# TestAdapter.net
KiCad netlist of a schematic drawn in EAGLE
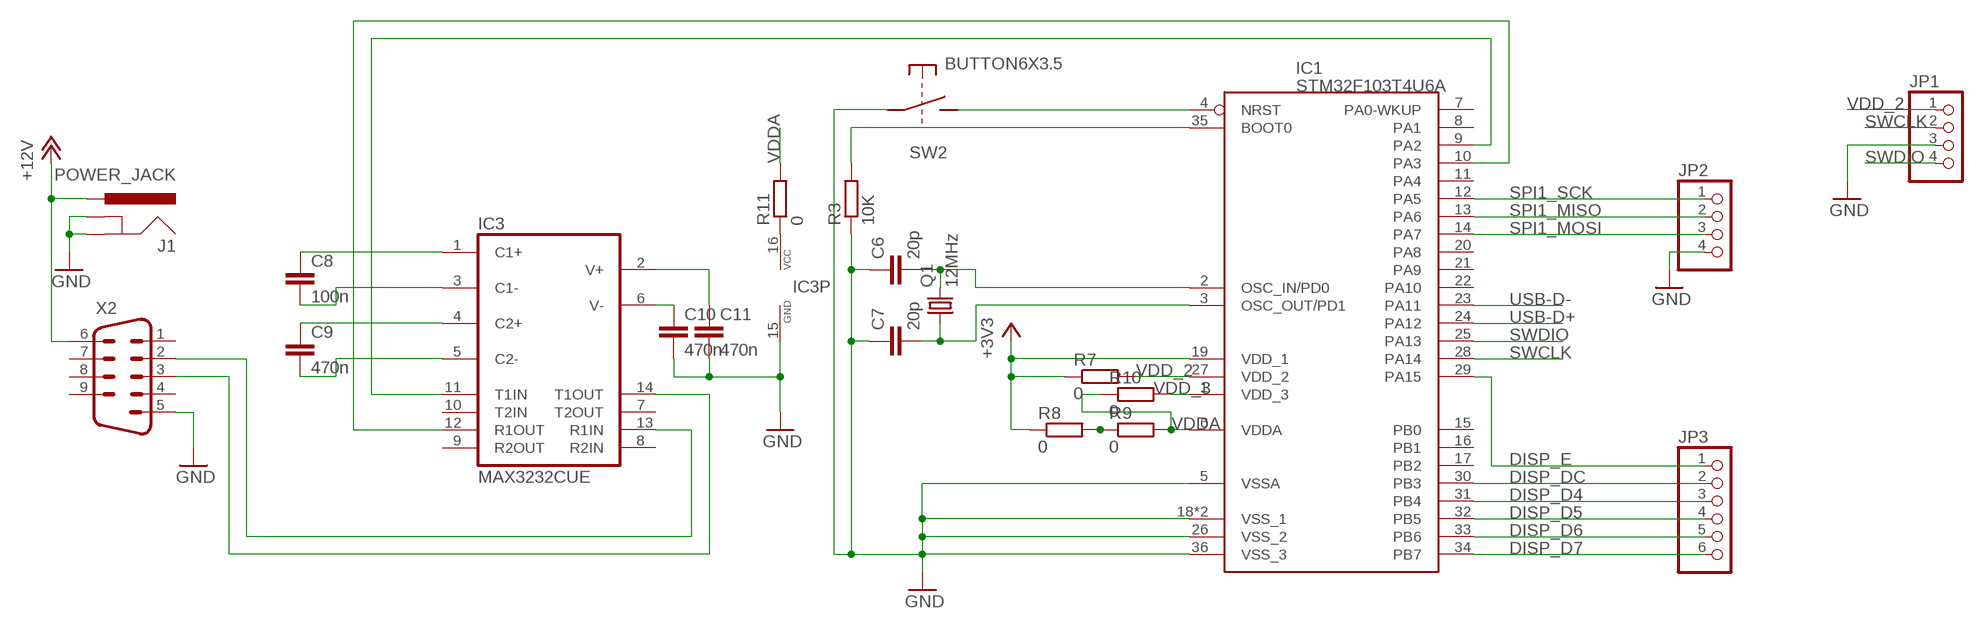
[diagram p0: schematic, sheet 1]
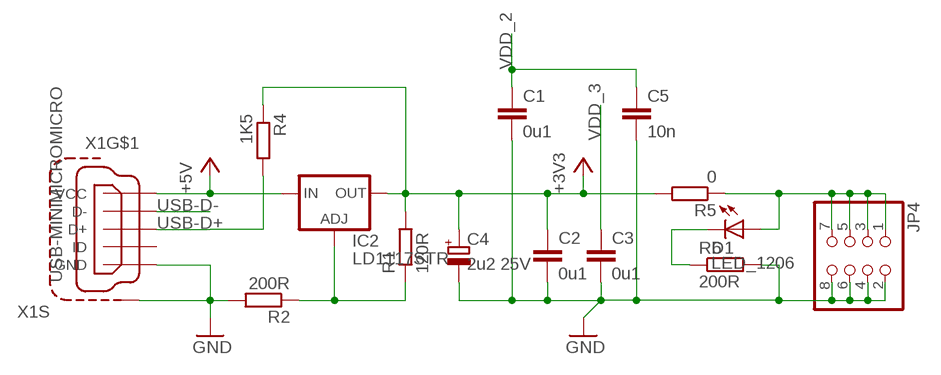
[diagram p1: schematic, sheet 2]

(export (version "E")
  (design (tool "Eeschema 10.0.6"))
  (components
    (comp (ref "C1")
      (value "0u1")
      (footprint "eagle-import:CAP0805")
      (libsource (lib "eagle-import") (part "CAP_0805"))
    )
    (comp (ref "C2")
      (value "0u1")
      (footprint "eagle-import:CAP0805")
      (libsource (lib "eagle-import") (part "CAP_0805"))
    )
    (comp (ref "C3")
      (value "0u1")
      (footprint "eagle-import:CAP0805")
      (libsource (lib "eagle-import") (part "CAP_0805"))
    )
    (comp (ref "C4")
      (value "2u2 25V")
      (footprint "eagle-import:CAPMP3317X180")
      (libsource (lib "eagle-import") (part "CAP-POL_CAPE3216-A"))
    )
    (comp (ref "C5")
      (value "10n")
      (footprint "eagle-import:CAP0805")
      (libsource (lib "eagle-import") (part "CAP_0805"))
    )
    (comp (ref "D1")
      (value "LED_1206")
      (footprint "eagle-import:LED1206")
      (libsource (lib "eagle-import") (part "LED_1206"))
    )
    (comp (ref "IC2")
      (value "LD1117STR")
      (footprint "eagle-import:SOT230P700X180-4")
      (libsource (lib "eagle-import") (part "VREG-ADJLD1117S"))
    )
    (comp (ref "JP4")
      (value "PINHD-2X4")
      (footprint "eagle-import:2X04")
      (libsource (lib "eagle-import") (part "PINHD-2X4"))
    )
    (comp (ref "R1")
      (value "120R")
      (footprint "eagle-import:RESC2012X50")
      (libsource (lib "eagle-import") (part "R_R0805"))
    )
    (comp (ref "R2")
      (value "200R")
      (footprint "eagle-import:RESC2012X50")
      (libsource (lib "eagle-import") (part "R_R0805"))
    )
    (comp (ref "R4")
      (value "1K5")
      (footprint "eagle-import:RESC2012X50")
      (libsource (lib "eagle-import") (part "R_R0805"))
    )
    (comp (ref "R5")
      (value "0")
      (footprint "eagle-import:RESC2012X50")
      (libsource (lib "eagle-import") (part "R_R0805"))
    )
    (comp (ref "R6")
      (value "200R")
      (footprint "eagle-import:RESC2012X50")
      (libsource (lib "eagle-import") (part "R_R0805"))
    )
    (comp (ref "X1")
      (value "USB-MINIMICROMICRO")
      (footprint "eagle-import:USB-B-MICRO-SMD")
      (libsource (lib "eagle-import") (part "USB-MINIMICROMICRO"))
    )
    (comp (ref "C6")
      (value "20p")
      (footprint "eagle-import:CAP0805")
      (libsource (lib "eagle-import") (part "CAP_0805"))
    )
    (comp (ref "C7")
      (value "20p")
      (footprint "eagle-import:CAP0805")
      (libsource (lib "eagle-import") (part "CAP_0805"))
    )
    (comp (ref "C8")
      (value "100n")
      (footprint "eagle-import:CAP0805")
      (libsource (lib "eagle-import") (part "CAP_0805"))
    )
    (comp (ref "C9")
      (value "470n")
      (footprint "eagle-import:CAP0805")
      (libsource (lib "eagle-import") (part "CAP_0805"))
    )
    (comp (ref "C10")
      (value "470n")
      (footprint "eagle-import:CAP0805")
      (libsource (lib "eagle-import") (part "CAP_0805"))
    )
    (comp (ref "C11")
      (value "470n")
      (footprint "eagle-import:CAP0805")
      (libsource (lib "eagle-import") (part "CAP_0805"))
    )
    (comp (ref "IC1")
      (value "STM32F103T4U6A")
      (footprint "eagle-import:QFN50P606X606X100-36")
      (libsource (lib "eagle-import") (part "STM32F103T4U6A"))
    )
    (comp (ref "IC3")
      (value "MAX3232CUE")
      (footprint "eagle-import:TSSOP16")
      (fields (field (name "MF") "MAXIM") (field (name "MPN") "MAX3232CUE+"))
      (libsource (lib "eagle-import") (part "MAX3232UEC"))
    )
    (comp (ref "J1")
      (value "POWER_JACK")
      (footprint "eagle-import:POWER_JACK_PTH")
      (libsource (lib "eagle-import") (part "POWER_JACK"))
    )
    (comp (ref "JP1")
      (value "PINHD-1X4")
      (footprint "eagle-import:1X04")
      (libsource (lib "eagle-import") (part "PINHD-1X4"))
    )
    (comp (ref "JP2")
      (value "PINHD-1X4")
      (footprint "eagle-import:1X04")
      (libsource (lib "eagle-import") (part "PINHD-1X4"))
    )
    (comp (ref "JP3")
      (value "PINHD-1X6")
      (footprint "eagle-import:1X06")
      (libsource (lib "eagle-import") (part "PINHD-1X6"))
    )
    (comp (ref "Q1")
      (value "12MHz")
      (footprint "eagle-import:CRYSTAL-5025")
      (libsource (lib "eagle-import") (part "CRYSTAL5032"))
    )
    (comp (ref "R3")
      (value "10K")
      (footprint "eagle-import:RESC2012X50")
      (libsource (lib "eagle-import") (part "R_R0805"))
    )
    (comp (ref "R7")
      (value "0")
      (footprint "eagle-import:RESC2012X50")
      (libsource (lib "eagle-import") (part "R_R0805"))
    )
    (comp (ref "R8")
      (value "0")
      (footprint "eagle-import:RESC2012X50")
      (libsource (lib "eagle-import") (part "R_R0805"))
    )
    (comp (ref "R9")
      (value "0")
      (footprint "eagle-import:RESC2012X50")
      (libsource (lib "eagle-import") (part "R_R0805"))
    )
    (comp (ref "R10")
      (value "0")
      (footprint "eagle-import:RESC2012X50")
      (libsource (lib "eagle-import") (part "R_R0805"))
    )
    (comp (ref "R11")
      (value "0")
      (footprint "eagle-import:RESC2012X50")
      (libsource (lib "eagle-import") (part "R_R0805"))
    )
    (comp (ref "SW2")
      (value "BUTTON6X3.5")
      (footprint "eagle-import:SW-6X3.5")
      (libsource (lib "eagle-import") (part "BUTTON6X3.5"))
    )
    (comp (ref "X2")
      (value "M09-182")
      (footprint "eagle-import:182-009-MALE")
      (libsource (lib "eagle-import") (part "M09-182"))
    )
  )
  (nets
    (net (code "1") (name "+3V3") (class "Default")
      (node (ref "C2") (pin "1") (pinfunction "1_1") (pintype "passive"))
      (node (ref "C4") (pin "1") (pinfunction "+_1") (pintype "passive"))
      (node (ref "IC1") (pin "19") (pinfunction "VDD_1_19") (pintype "power_in"))
      (node (ref "IC2") (pin "2") (pinfunction "OUT_2") (pintype "passive"))
      (node (ref "IC2") (pin "4") (pinfunction "OUT_4") (pintype "passive"))
      (node (ref "R1") (pin "2") (pinfunction "2_2") (pintype "passive"))
      (node (ref "R4") (pin "1") (pinfunction "1_1") (pintype "passive"))
      (node (ref "R5") (pin "2") (pinfunction "2_2") (pintype "passive"))
      (node (ref "R7") (pin "1") (pinfunction "1_1") (pintype "passive"))
      (node (ref "R8") (pin "1") (pinfunction "1_1") (pintype "passive"))
    )
    (net (code "2") (name "+5V") (class "Default")
      (node (ref "IC2") (pin "3") (pinfunction "IN_3") (pintype "input"))
      (node (ref "X1") (pin "VBUS") (pinfunction "VCC_VBUS") (pintype "passive"))
    )
    (net (code "3") (name "+12V") (class "Default")
      (node (ref "J1") (pin "PWR") (pinfunction "PWR_PWR") (pintype "bidirectional"))
      (node (ref "X2") (pin "6") (pinfunction "6_6") (pintype "passive"))
    )
    (net (code "4") (name "DISP_D4") (class "Default")
      (node (ref "IC1") (pin "31") (pinfunction "PB4_31") (pintype "bidirectional"))
      (node (ref "JP3") (pin "3") (pinfunction "3_3") (pintype "passive"))
    )
    (net (code "5") (name "DISP_D5") (class "Default")
      (node (ref "IC1") (pin "32") (pinfunction "PB5_32") (pintype "bidirectional"))
      (node (ref "JP3") (pin "4") (pinfunction "4_4") (pintype "passive"))
    )
    (net (code "6") (name "DISP_D6") (class "Default")
      (node (ref "IC1") (pin "33") (pinfunction "PB6_33") (pintype "bidirectional"))
      (node (ref "JP3") (pin "5") (pinfunction "5_5") (pintype "passive"))
    )
    (net (code "7") (name "DISP_D7") (class "Default")
      (node (ref "IC1") (pin "34") (pinfunction "PB7_34") (pintype "bidirectional"))
      (node (ref "JP3") (pin "6") (pinfunction "6_6") (pintype "passive"))
    )
    (net (code "8") (name "DISP_DC") (class "Default")
      (node (ref "IC1") (pin "30") (pinfunction "PB3_30") (pintype "bidirectional"))
      (node (ref "JP3") (pin "2") (pinfunction "2_2") (pintype "passive"))
    )
    (net (code "9") (name "DISP_E") (class "Default")
      (node (ref "IC1") (pin "29") (pinfunction "PA15_29") (pintype "bidirectional"))
      (node (ref "JP3") (pin "1") (pinfunction "1_1") (pintype "passive"))
    )
    (net (code "10") (name "GND") (class "Default")
      (node (ref "C1") (pin "2") (pinfunction "2_2") (pintype "passive"))
      (node (ref "C10") (pin "2") (pinfunction "2_2") (pintype "passive"))
      (node (ref "C11") (pin "2") (pinfunction "2_2") (pintype "passive"))
      (node (ref "C2") (pin "2") (pinfunction "2_2") (pintype "passive"))
      (node (ref "C3") (pin "2") (pinfunction "2_2") (pintype "passive"))
      (node (ref "C4") (pin "2") (pinfunction "-_2") (pintype "passive"))
      (node (ref "C5") (pin "2") (pinfunction "2_2") (pintype "passive"))
      (node (ref "C6") (pin "1") (pinfunction "1_1") (pintype "passive"))
      (node (ref "C7") (pin "1") (pinfunction "1_1") (pintype "passive"))
      (node (ref "IC1") (pin "18") (pinfunction "VSS_1_18") (pintype "power_in"))
      (node (ref "IC1") (pin "26") (pinfunction "VSS_2_26") (pintype "power_in"))
      (node (ref "IC1") (pin "36") (pinfunction "VSS_3_36") (pintype "power_in"))
      (node (ref "IC1") (pin "5") (pinfunction "VSSA_5") (pintype "power_in"))
      (node (ref "IC1") (pin "P$1") (pinfunction "VSS_1_P$1") (pintype "power_in"))
      (node (ref "IC3") (pin "15") (pinfunction "GND_15") (pintype "power_in"))
      (node (ref "J1") (pin "GND") (pinfunction "GND_GND") (pintype "bidirectional"))
      (node (ref "J1") (pin "GNDBREAK") (pinfunction "GNDBREAK_GNDBREAK") (pintype "bidirectional"))
      (node (ref "JP1") (pin "3") (pinfunction "3_3") (pintype "passive"))
      (node (ref "JP2") (pin "4") (pinfunction "4_4") (pintype "passive"))
      (node (ref "JP4") (pin "2") (pinfunction "2_2") (pintype "passive"))
      (node (ref "JP4") (pin "4") (pinfunction "4_4") (pintype "passive"))
      (node (ref "JP4") (pin "6") (pinfunction "6_6") (pintype "passive"))
      (node (ref "JP4") (pin "8") (pinfunction "8_8") (pintype "passive"))
      (node (ref "R2") (pin "2") (pinfunction "2_2") (pintype "passive"))
      (node (ref "R3") (pin "1") (pinfunction "1_1") (pintype "passive"))
      (node (ref "R6") (pin "2") (pinfunction "2_2") (pintype "passive"))
      (node (ref "SW2") (pin "1") (pinfunction "1_1") (pintype "passive"))
      (node (ref "X1") (pin "GND") (pinfunction "GND_GND") (pintype "passive"))
      (node (ref "X1") (pin "SHIELD1") (pinfunction "S1_SHIELD1") (pintype "passive"))
      (node (ref "X1") (pin "SHIELD2") (pinfunction "S1_SHIELD2") (pintype "passive"))
      (node (ref "X1") (pin "SHIELD3") (pinfunction "S1_SHIELD3") (pintype "passive"))
      (node (ref "X2") (pin "5") (pinfunction "5_5") (pintype "passive"))
    )
    (net (code "11") (name "Net-(D1-PadA)") (class "Default")
      (node (ref "D1") (pin "A") (pinfunction "A_A") (pintype "passive"))
      (node (ref "JP4") (pin "1") (pinfunction "1_1") (pintype "passive"))
      (node (ref "JP4") (pin "3") (pinfunction "3_3") (pintype "passive"))
      (node (ref "JP4") (pin "5") (pinfunction "5_5") (pintype "passive"))
      (node (ref "JP4") (pin "7") (pinfunction "7_7") (pintype "passive"))
      (node (ref "R5") (pin "1") (pinfunction "1_1") (pintype "passive"))
    )
    (net (code "12") (name "Net-(D1-PadC)") (class "Default")
      (node (ref "D1") (pin "C") (pinfunction "C_C") (pintype "passive"))
      (node (ref "R6") (pin "1") (pinfunction "1_1") (pintype "passive"))
    )
    (net (code "13") (name "Net-(IC1-BOOT0)") (class "Default")
      (node (ref "IC1") (pin "35") (pinfunction "BOOT0_35") (pintype "bidirectional"))
      (node (ref "R3") (pin "2") (pinfunction "2_2") (pintype "passive"))
    )
    (net (code "14") (name "Net-(IC1-NRST)") (class "Default")
      (node (ref "IC1") (pin "4") (pinfunction "NRST_4") (pintype "bidirectional"))
      (node (ref "SW2") (pin "2") (pinfunction "2_2") (pintype "passive"))
    )
    (net (code "15") (name "Net-(IC1-OSC_IN{slash}PD0)") (class "Default")
      (node (ref "C6") (pin "2") (pinfunction "2_2") (pintype "passive"))
      (node (ref "IC1") (pin "2") (pinfunction "OSC_IN/PD0_2") (pintype "bidirectional"))
      (node (ref "Q1") (pin "P$2") (pinfunction "2_P$2") (pintype "passive"))
    )
    (net (code "16") (name "Net-(IC1-OSC_OUT{slash}PD1)") (class "Default")
      (node (ref "C7") (pin "2") (pinfunction "2_2") (pintype "passive"))
      (node (ref "IC1") (pin "3") (pinfunction "OSC_OUT/PD1_3") (pintype "bidirectional"))
      (node (ref "Q1") (pin "P$1") (pinfunction "1_P$1") (pintype "passive"))
    )
    (net (code "17") (name "Net-(IC1-PA2)") (class "Default")
      (node (ref "IC1") (pin "9") (pinfunction "PA2_9") (pintype "bidirectional"))
      (node (ref "IC3") (pin "11") (pinfunction "T1IN_11") (pintype "input"))
    )
    (net (code "18") (name "Net-(IC1-PA3)") (class "Default")
      (node (ref "IC1") (pin "10") (pinfunction "PA3_10") (pintype "bidirectional"))
      (node (ref "IC3") (pin "12") (pinfunction "R1OUT_12") (pintype "output"))
    )
    (net (code "19") (name "Net-(IC2-ADJ)") (class "Default")
      (node (ref "IC2") (pin "1") (pinfunction "ADJ_1") (pintype "input"))
      (node (ref "R1") (pin "1") (pinfunction "1_1") (pintype "passive"))
      (node (ref "R2") (pin "1") (pinfunction "1_1") (pintype "passive"))
    )
    (net (code "20") (name "Net-(IC3A-C1+)") (class "Default")
      (node (ref "C8") (pin "1") (pinfunction "1_1") (pintype "passive"))
      (node (ref "IC3") (pin "1") (pinfunction "C1+_1") (pintype "bidirectional"))
    )
    (net (code "21") (name "Net-(IC3A-C1-)") (class "Default")
      (node (ref "C8") (pin "2") (pinfunction "2_2") (pintype "passive"))
      (node (ref "IC3") (pin "3") (pinfunction "C1-_3") (pintype "bidirectional"))
    )
    (net (code "22") (name "Net-(IC3A-C2+)") (class "Default")
      (node (ref "C9") (pin "1") (pinfunction "1_1") (pintype "passive"))
      (node (ref "IC3") (pin "4") (pinfunction "C2+_4") (pintype "bidirectional"))
    )
    (net (code "23") (name "Net-(IC3A-C2-)") (class "Default")
      (node (ref "C9") (pin "2") (pinfunction "2_2") (pintype "passive"))
      (node (ref "IC3") (pin "5") (pinfunction "C2-_5") (pintype "bidirectional"))
    )
    (net (code "24") (name "Net-(IC3A-R1IN)") (class "Default")
      (node (ref "IC3") (pin "13") (pinfunction "R1IN_13") (pintype "input"))
      (node (ref "X2") (pin "2") (pinfunction "2_2") (pintype "passive"))
    )
    (net (code "25") (name "Net-(IC3A-T1OUT)") (class "Default")
      (node (ref "IC3") (pin "14") (pinfunction "T1OUT_14") (pintype "output"))
      (node (ref "X2") (pin "3") (pinfunction "3_3") (pintype "passive"))
    )
    (net (code "26") (name "Net-(IC3A-V+)") (class "Default")
      (node (ref "C11") (pin "1") (pinfunction "1_1") (pintype "passive"))
      (node (ref "IC3") (pin "2") (pinfunction "V+_2") (pintype "bidirectional"))
    )
    (net (code "27") (name "Net-(IC3A-V-)") (class "Default")
      (node (ref "C10") (pin "1") (pinfunction "1_1") (pintype "passive"))
      (node (ref "IC3") (pin "6") (pinfunction "V-_6") (pintype "bidirectional"))
    )
    (net (code "28") (name "Net-(IC3B-VCC)") (class "Default")
      (node (ref "IC3") (pin "16") (pinfunction "VCC_16") (pintype "power_in"))
      (node (ref "R11") (pin "1") (pinfunction "1_1") (pintype "passive"))
    )
    (net (code "29") (name "Net-(R8-Pad2)") (class "Default")
      (node (ref "R8") (pin "2") (pinfunction "2_2") (pintype "passive"))
      (node (ref "R9") (pin "1") (pinfunction "1_1") (pintype "passive"))
    )
    (net (code "30") (name "SPI1_MISO") (class "Default")
      (node (ref "IC1") (pin "13") (pinfunction "PA6_13") (pintype "bidirectional"))
      (node (ref "JP2") (pin "2") (pinfunction "2_2") (pintype "passive"))
    )
    (net (code "31") (name "SPI1_MOSI") (class "Default")
      (node (ref "IC1") (pin "14") (pinfunction "PA7_14") (pintype "bidirectional"))
      (node (ref "JP2") (pin "3") (pinfunction "3_3") (pintype "passive"))
    )
    (net (code "32") (name "SPI1_SCK") (class "Default")
      (node (ref "IC1") (pin "12") (pinfunction "PA5_12") (pintype "bidirectional"))
      (node (ref "JP2") (pin "1") (pinfunction "1_1") (pintype "passive"))
    )
    (net (code "33") (name "SWCLK") (class "Default")
      (node (ref "IC1") (pin "28") (pinfunction "PA14_28") (pintype "bidirectional"))
      (node (ref "JP1") (pin "2") (pinfunction "2_2") (pintype "passive"))
    )
    (net (code "34") (name "SWDIO") (class "Default")
      (node (ref "IC1") (pin "25") (pinfunction "PA13_25") (pintype "bidirectional"))
      (node (ref "JP1") (pin "4") (pinfunction "4_4") (pintype "passive"))
    )
    (net (code "35") (name "USB-D+") (class "Default")
      (node (ref "IC1") (pin "24") (pinfunction "PA12_24") (pintype "bidirectional"))
      (node (ref "R4") (pin "2") (pinfunction "2_2") (pintype "passive"))
      (node (ref "X1") (pin "D+") (pinfunction "D+_D+") (pintype "passive"))
    )
    (net (code "36") (name "USB-D-") (class "Default")
      (node (ref "IC1") (pin "23") (pinfunction "PA11_23") (pintype "bidirectional"))
      (node (ref "X1") (pin "D-") (pinfunction "D-_D-") (pintype "passive"))
    )
    (net (code "37") (name "VDDA") (class "Default")
      (node (ref "IC1") (pin "6") (pinfunction "VDDA_6") (pintype "power_in"))
      (node (ref "R10") (pin "1") (pinfunction "1_1") (pintype "passive"))
      (node (ref "R11") (pin "2") (pinfunction "2_2") (pintype "passive"))
      (node (ref "R9") (pin "2") (pinfunction "2_2") (pintype "passive"))
    )
    (net (code "38") (name "VDD_2") (class "Default")
      (node (ref "C1") (pin "1") (pinfunction "1_1") (pintype "passive"))
      (node (ref "C5") (pin "1") (pinfunction "1_1") (pintype "passive"))
      (node (ref "IC1") (pin "27") (pinfunction "VDD_2_27") (pintype "power_in"))
      (node (ref "JP1") (pin "1") (pinfunction "1_1") (pintype "passive"))
      (node (ref "R7") (pin "2") (pinfunction "2_2") (pintype "passive"))
    )
    (net (code "39") (name "VDD_3") (class "Default")
      (node (ref "C3") (pin "1") (pinfunction "1_1") (pintype "passive"))
      (node (ref "IC1") (pin "1") (pinfunction "VDD_3_1") (pintype "power_in"))
      (node (ref "R10") (pin "2") (pinfunction "2_2") (pintype "passive"))
    )
    (net (code "40") (name "unconnected-(IC1-PA0-WKUP-Pad7)") (class "Default")
      (node (ref "IC1") (pin "7") (pinfunction "PA0-WKUP_7") (pintype "bidirectional"))
    )
    (net (code "41") (name "unconnected-(IC1-PA1-Pad8)") (class "Default")
      (node (ref "IC1") (pin "8") (pinfunction "PA1_8") (pintype "bidirectional"))
    )
    (net (code "42") (name "unconnected-(IC1-PA4-Pad11)") (class "Default")
      (node (ref "IC1") (pin "11") (pinfunction "PA4_11") (pintype "bidirectional"))
    )
    (net (code "43") (name "unconnected-(IC1-PA8-Pad20)") (class "Default")
      (node (ref "IC1") (pin "20") (pinfunction "PA8_20") (pintype "bidirectional"))
    )
    (net (code "44") (name "unconnected-(IC1-PA9-Pad21)") (class "Default")
      (node (ref "IC1") (pin "21") (pinfunction "PA9_21") (pintype "bidirectional"))
    )
    (net (code "45") (name "unconnected-(IC1-PA10-Pad22)") (class "Default")
      (node (ref "IC1") (pin "22") (pinfunction "PA10_22") (pintype "bidirectional"))
    )
    (net (code "46") (name "unconnected-(IC1-PB0-Pad15)") (class "Default")
      (node (ref "IC1") (pin "15") (pinfunction "PB0_15") (pintype "bidirectional"))
    )
    (net (code "47") (name "unconnected-(IC1-PB1-Pad16)") (class "Default")
      (node (ref "IC1") (pin "16") (pinfunction "PB1_16") (pintype "bidirectional"))
    )
    (net (code "48") (name "unconnected-(IC1-PB2-Pad17)") (class "Default")
      (node (ref "IC1") (pin "17") (pinfunction "PB2_17") (pintype "bidirectional"))
    )
    (net (code "49") (name "unconnected-(IC3A-R2IN-Pad8)") (class "Default")
      (node (ref "IC3") (pin "8") (pinfunction "R2IN_8") (pintype "input"))
    )
    (net (code "50") (name "unconnected-(IC3A-R2OUT-Pad9)") (class "Default")
      (node (ref "IC3") (pin "9") (pinfunction "R2OUT_9") (pintype "output"))
    )
    (net (code "51") (name "unconnected-(IC3A-T2IN-Pad10)") (class "Default")
      (node (ref "IC3") (pin "10") (pinfunction "T2IN_10") (pintype "input"))
    )
    (net (code "52") (name "unconnected-(IC3A-T2OUT-Pad7)") (class "Default")
      (node (ref "IC3") (pin "7") (pinfunction "T2OUT_7") (pintype "output"))
    )
    (net (code "53") (name "unconnected-(X1-PadID)") (class "Default")
      (node (ref "X1") (pin "ID") (pinfunction "ID_ID") (pintype "passive"))
    )
    (net (code "54") (name "unconnected-(X2-Pad1)") (class "Default")
      (node (ref "X2") (pin "1") (pinfunction "1_1") (pintype "passive"))
    )
    (net (code "55") (name "unconnected-(X2-Pad4)") (class "Default")
      (node (ref "X2") (pin "4") (pinfunction "4_4") (pintype "passive"))
    )
    (net (code "56") (name "unconnected-(X2-Pad7)") (class "Default")
      (node (ref "X2") (pin "7") (pinfunction "7_7") (pintype "passive"))
    )
    (net (code "57") (name "unconnected-(X2-Pad8)") (class "Default")
      (node (ref "X2") (pin "8") (pinfunction "8_8") (pintype "passive"))
    )
    (net (code "58") (name "unconnected-(X2-Pad9)") (class "Default")
      (node (ref "X2") (pin "9") (pinfunction "9_9") (pintype "passive"))
    )
  )
)
